# Enclosure_control.net
KiCad netlist of a schematic drawn in EAGLE
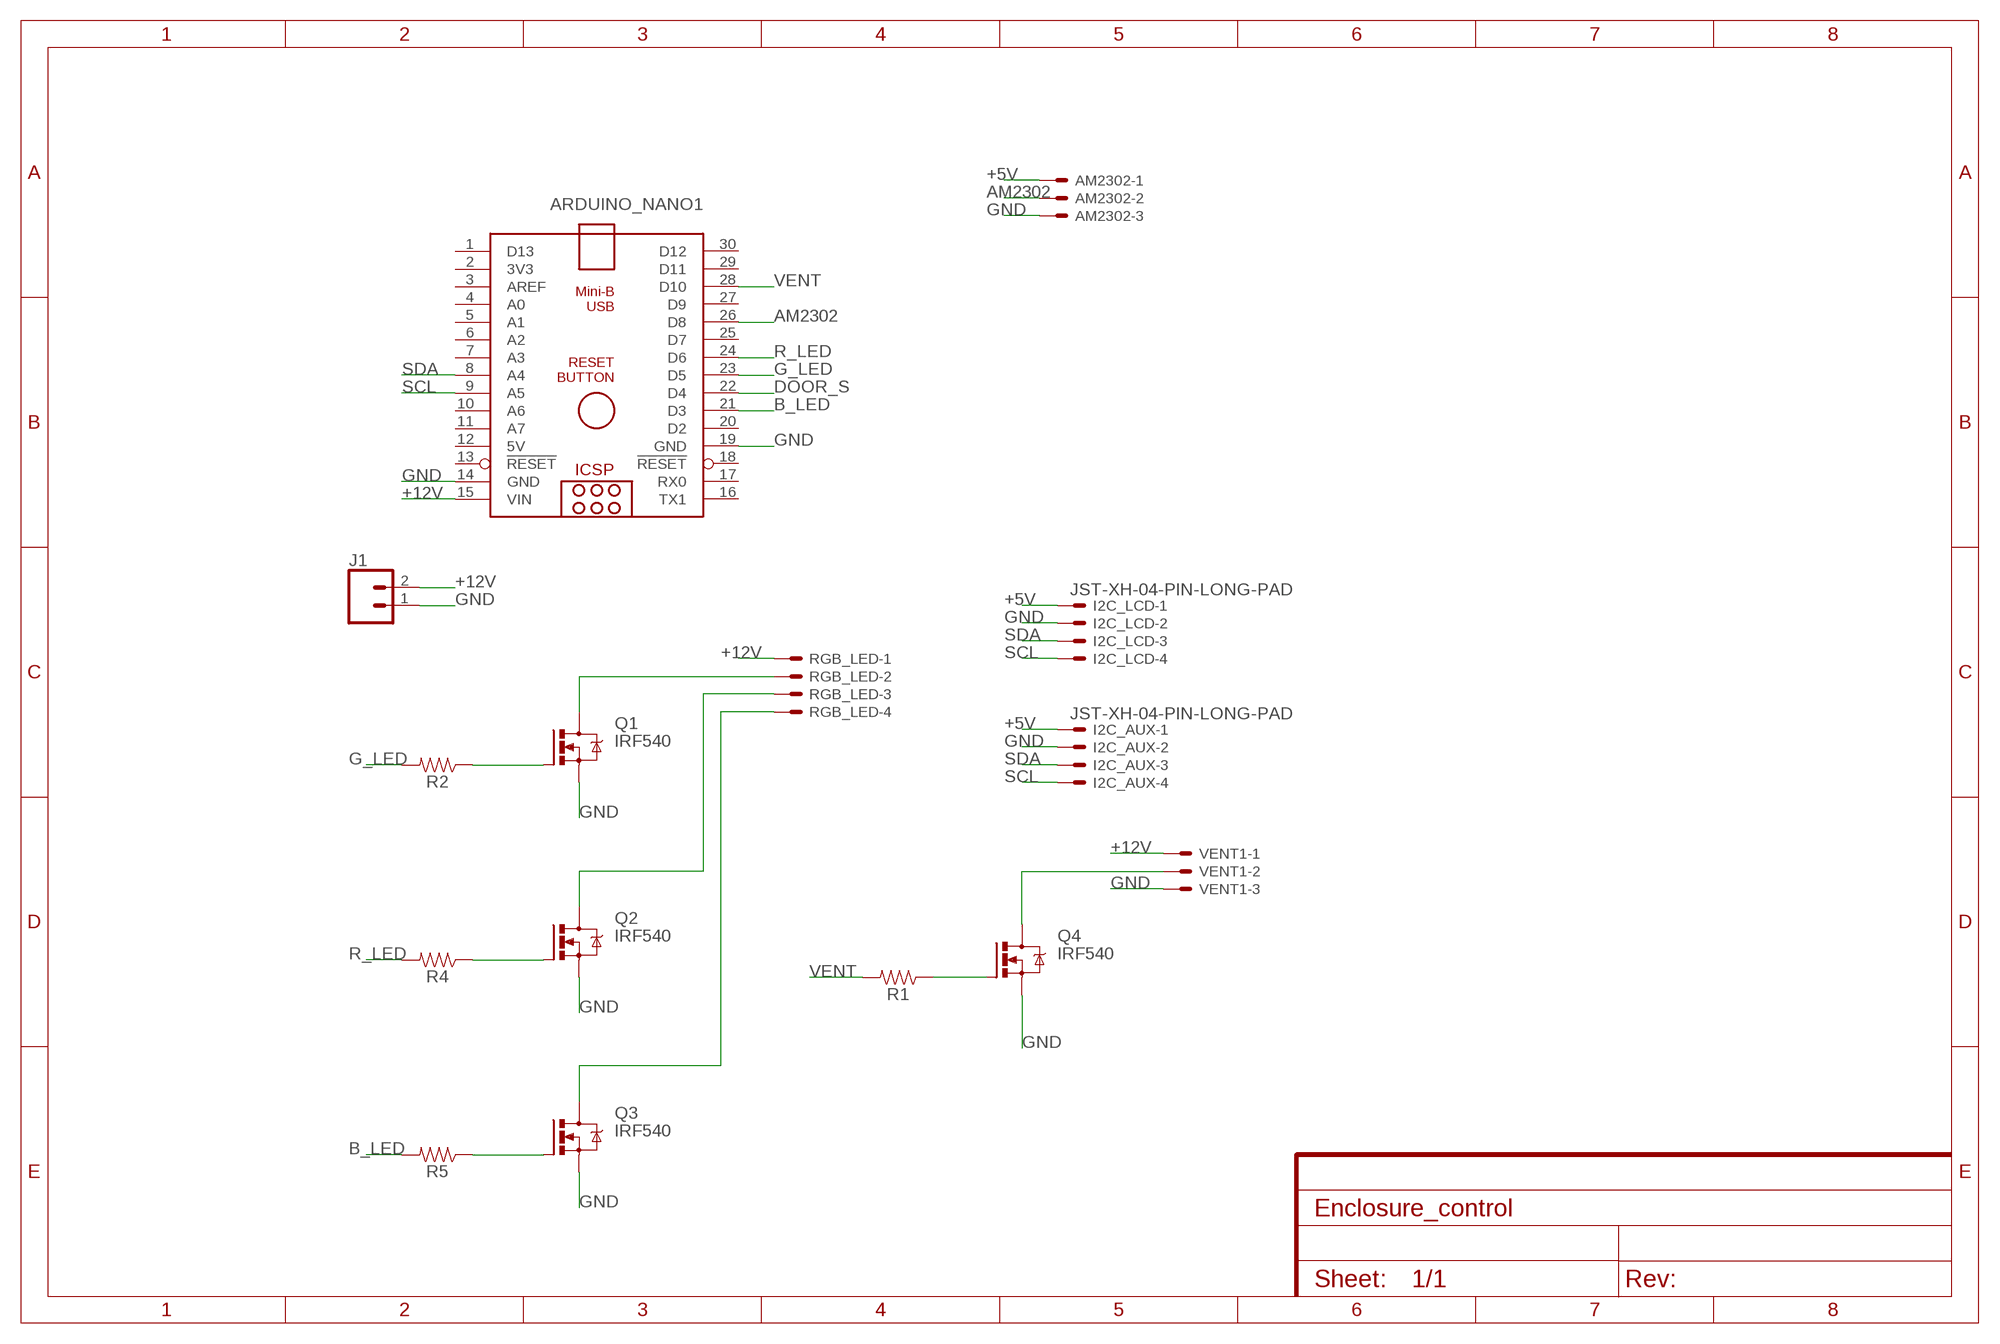
[diagram p0: schematic, sheet 1]

(export (version "E")
  (design (tool "Eeschema 10.0.6"))
  (components
    (comp (ref "AM2302")
      (value "KK-156-3")
      (footprint "eagle-import:KK-156-3")
      (fields (field (name "MF") "MOLEX"))
      (libsource (lib "eagle-import") (part "KK-156-3"))
    )
    (comp (ref "ARDUINO_NANO1")
      (value "ARDUINO_NANO")
      (footprint "eagle-import:ARDUINO_NANO")
      (libsource (lib "eagle-import") (part "ARDUINO_NANO"))
    )
    (comp (ref "I2C_AUX")
      (value "JST-XH-04-PIN-LONG-PAD")
      (footprint "eagle-import:JST-XH-04-PACKAGE-LONG-PAD")
      (libsource (lib "eagle-import") (part "JST-XH-04-PIN-LONG-PAD"))
    )
    (comp (ref "I2C_LCD")
      (value "JST-XH-04-PIN-LONG-PAD")
      (footprint "eagle-import:JST-XH-04-PACKAGE-LONG-PAD")
      (libsource (lib "eagle-import") (part "JST-XH-04-PIN-LONG-PAD"))
    )
    (comp (ref "J1")
      (value "CONN_02PTH4")
      (footprint "eagle-import:1X02_XTRA_BIG")
      (libsource (lib "eagle-import") (part "CONN_02PTH4"))
    )
    (comp (ref "Q1")
      (value "IRF540")
      (footprint "eagle-import:TO220BV")
      (libsource (lib "eagle-import") (part "IRF540"))
    )
    (comp (ref "Q2")
      (value "IRF540")
      (footprint "eagle-import:TO220BV")
      (libsource (lib "eagle-import") (part "IRF540"))
    )
    (comp (ref "Q3")
      (value "IRF540")
      (footprint "eagle-import:TO220BV")
      (libsource (lib "eagle-import") (part "IRF540"))
    )
    (comp (ref "Q4")
      (value "IRF540")
      (footprint "eagle-import:TO220BV")
      (libsource (lib "eagle-import") (part "IRF540"))
    )
    (comp (ref "R1")
      (value "RESISTORAXIAL-0.3")
      (footprint "eagle-import:AXIAL-0.3")
      (libsource (lib "eagle-import") (part "RESISTORAXIAL-0.3"))
    )
    (comp (ref "R2")
      (value "RESISTORAXIAL-0.3")
      (footprint "eagle-import:AXIAL-0.3")
      (libsource (lib "eagle-import") (part "RESISTORAXIAL-0.3"))
    )
    (comp (ref "R4")
      (value "RESISTORAXIAL-0.3")
      (footprint "eagle-import:AXIAL-0.3")
      (libsource (lib "eagle-import") (part "RESISTORAXIAL-0.3"))
    )
    (comp (ref "R5")
      (value "RESISTORAXIAL-0.3")
      (footprint "eagle-import:AXIAL-0.3")
      (libsource (lib "eagle-import") (part "RESISTORAXIAL-0.3"))
    )
    (comp (ref "RGB_LED")
      (value "KK-156-4")
      (footprint "eagle-import:KK-156-4")
      (fields (field (name "MF") "MOLEX"))
      (libsource (lib "eagle-import") (part "KK-156-4"))
    )
    (comp (ref "VENT1")
      (value "KK-156-3")
      (footprint "eagle-import:KK-156-3")
      (fields (field (name "MF") "MOLEX"))
      (libsource (lib "eagle-import") (part "KK-156-3"))
    )
  )
  (nets
    (net (code "1") (name "/+5V") (class "Default")
      (node (ref "AM2302") (pin "1") (pinfunction "S_1") (pintype "passive"))
      (node (ref "I2C_AUX") (pin "1") (pinfunction "S_1") (pintype "passive"))
      (node (ref "I2C_LCD") (pin "1") (pinfunction "S_1") (pintype "passive"))
    )
    (net (code "2") (name "/+12V") (class "Default")
      (node (ref "ARDUINO_NANO1") (pin "15") (pinfunction "VIN_15") (pintype "power_in"))
      (node (ref "J1") (pin "2") (pinfunction "2_2") (pintype "passive"))
      (node (ref "RGB_LED") (pin "1") (pinfunction "S_1") (pintype "passive"))
      (node (ref "VENT1") (pin "1") (pinfunction "S_1") (pintype "passive"))
    )
    (net (code "3") (name "/5V") (class "Default")
      (node (ref "ARDUINO_NANO1") (pin "12") (pinfunction "5V_12") (pintype "power_in"))
    )
    (net (code "4") (name "/AM2302") (class "Default")
      (node (ref "AM2302") (pin "2") (pinfunction "S_2") (pintype "passive"))
      (node (ref "ARDUINO_NANO1") (pin "26") (pinfunction "D8_26") (pintype "bidirectional"))
    )
    (net (code "5") (name "/B_LED") (class "Default")
      (node (ref "ARDUINO_NANO1") (pin "21") (pinfunction "D3_21") (pintype "bidirectional"))
      (node (ref "R5") (pin "P$2") (pinfunction "2_P$2") (pintype "passive"))
    )
    (net (code "6") (name "/DOOR_S") (class "Default")
      (node (ref "ARDUINO_NANO1") (pin "22") (pinfunction "D4_22") (pintype "bidirectional"))
    )
    (net (code "7") (name "/GND") (class "Default")
      (node (ref "AM2302") (pin "3") (pinfunction "S_3") (pintype "passive"))
      (node (ref "ARDUINO_NANO1") (pin "14") (pinfunction "GND_14") (pintype "power_in"))
      (node (ref "ARDUINO_NANO1") (pin "19") (pinfunction "GND_19") (pintype "power_in"))
      (node (ref "I2C_AUX") (pin "2") (pinfunction "S_2") (pintype "passive"))
      (node (ref "I2C_LCD") (pin "2") (pinfunction "S_2") (pintype "passive"))
      (node (ref "J1") (pin "1") (pinfunction "1_1") (pintype "passive"))
      (node (ref "Q1") (pin "S") (pinfunction "S_S") (pintype "passive"))
      (node (ref "Q2") (pin "S") (pinfunction "S_S") (pintype "passive"))
      (node (ref "Q3") (pin "S") (pinfunction "S_S") (pintype "passive"))
      (node (ref "Q4") (pin "S") (pinfunction "S_S") (pintype "passive"))
      (node (ref "VENT1") (pin "3") (pinfunction "S_3") (pintype "passive"))
    )
    (net (code "8") (name "/G_LED") (class "Default")
      (node (ref "ARDUINO_NANO1") (pin "23") (pinfunction "D5_23") (pintype "bidirectional"))
      (node (ref "R2") (pin "P$2") (pinfunction "2_P$2") (pintype "passive"))
    )
    (net (code "9") (name "/R_LED") (class "Default")
      (node (ref "ARDUINO_NANO1") (pin "24") (pinfunction "D6_24") (pintype "bidirectional"))
      (node (ref "R4") (pin "P$2") (pinfunction "2_P$2") (pintype "passive"))
    )
    (net (code "10") (name "/SCL") (class "Default")
      (node (ref "ARDUINO_NANO1") (pin "9") (pinfunction "A5_9") (pintype "bidirectional"))
      (node (ref "I2C_AUX") (pin "4") (pinfunction "S_4") (pintype "passive"))
      (node (ref "I2C_LCD") (pin "4") (pinfunction "S_4") (pintype "passive"))
    )
    (net (code "11") (name "/SDA") (class "Default")
      (node (ref "ARDUINO_NANO1") (pin "8") (pinfunction "A4_8") (pintype "bidirectional"))
      (node (ref "I2C_AUX") (pin "3") (pinfunction "S_3") (pintype "passive"))
      (node (ref "I2C_LCD") (pin "3") (pinfunction "S_3") (pintype "passive"))
    )
    (net (code "12") (name "/VENT") (class "Default")
      (node (ref "ARDUINO_NANO1") (pin "28") (pinfunction "D10_28") (pintype "bidirectional"))
      (node (ref "R1") (pin "P$2") (pinfunction "2_P$2") (pintype "passive"))
    )
    (net (code "13") (name "Net-(R1-1)") (class "Default")
      (node (ref "Q4") (pin "G") (pinfunction "G_G") (pintype "passive"))
      (node (ref "R1") (pin "P$1") (pinfunction "1_P$1") (pintype "passive"))
    )
    (net (code "14") (name "Net-(R2-1)") (class "Default")
      (node (ref "Q1") (pin "G") (pinfunction "G_G") (pintype "passive"))
      (node (ref "R2") (pin "P$1") (pinfunction "1_P$1") (pintype "passive"))
    )
    (net (code "15") (name "Net-(R4-1)") (class "Default")
      (node (ref "Q2") (pin "G") (pinfunction "G_G") (pintype "passive"))
      (node (ref "R4") (pin "P$1") (pinfunction "1_P$1") (pintype "passive"))
    )
    (net (code "16") (name "Net-(R5-1)") (class "Default")
      (node (ref "Q3") (pin "G") (pinfunction "G_G") (pintype "passive"))
      (node (ref "R5") (pin "P$1") (pinfunction "1_P$1") (pintype "passive"))
    )
    (net (code "17") (name "Net-(RGB_LEDB-S)") (class "Default")
      (node (ref "Q1") (pin "D") (pinfunction "D_D") (pintype "passive"))
      (node (ref "RGB_LED") (pin "2") (pinfunction "S_2") (pintype "passive"))
    )
    (net (code "18") (name "Net-(RGB_LEDC-S)") (class "Default")
      (node (ref "Q2") (pin "D") (pinfunction "D_D") (pintype "passive"))
      (node (ref "RGB_LED") (pin "3") (pinfunction "S_3") (pintype "passive"))
    )
    (net (code "19") (name "Net-(RGB_LEDD-S)") (class "Default")
      (node (ref "Q3") (pin "D") (pinfunction "D_D") (pintype "passive"))
      (node (ref "RGB_LED") (pin "4") (pinfunction "S_4") (pintype "passive"))
    )
    (net (code "20") (name "Net-(VENT1B-S)") (class "Default")
      (node (ref "Q4") (pin "D") (pinfunction "D_D") (pintype "passive"))
      (node (ref "VENT1") (pin "2") (pinfunction "S_2") (pintype "passive"))
    )
    (net (code "21") (name "unconnected-(ARDUINO_NANO1-3V3-Pad2)") (class "Default")
      (node (ref "ARDUINO_NANO1") (pin "2") (pinfunction "3V3_2") (pintype "output"))
    )
    (net (code "22") (name "unconnected-(ARDUINO_NANO1-A0-Pad4)") (class "Default")
      (node (ref "ARDUINO_NANO1") (pin "4") (pinfunction "A0_4") (pintype "bidirectional"))
    )
    (net (code "23") (name "unconnected-(ARDUINO_NANO1-A1-Pad5)") (class "Default")
      (node (ref "ARDUINO_NANO1") (pin "5") (pinfunction "A1_5") (pintype "bidirectional"))
    )
    (net (code "24") (name "unconnected-(ARDUINO_NANO1-A2-Pad6)") (class "Default")
      (node (ref "ARDUINO_NANO1") (pin "6") (pinfunction "A2_6") (pintype "bidirectional"))
    )
    (net (code "25") (name "unconnected-(ARDUINO_NANO1-A3-Pad7)") (class "Default")
      (node (ref "ARDUINO_NANO1") (pin "7") (pinfunction "A3_7") (pintype "bidirectional"))
    )
    (net (code "26") (name "unconnected-(ARDUINO_NANO1-A6-Pad10)") (class "Default")
      (node (ref "ARDUINO_NANO1") (pin "10") (pinfunction "A6_10") (pintype "bidirectional"))
    )
    (net (code "27") (name "unconnected-(ARDUINO_NANO1-A7-Pad11)") (class "Default")
      (node (ref "ARDUINO_NANO1") (pin "11") (pinfunction "A7_11") (pintype "bidirectional"))
    )
    (net (code "28") (name "unconnected-(ARDUINO_NANO1-AREF-Pad3)") (class "Default")
      (node (ref "ARDUINO_NANO1") (pin "3") (pinfunction "AREF_3") (pintype "input"))
    )
    (net (code "29") (name "unconnected-(ARDUINO_NANO1-D2-Pad20)") (class "Default")
      (node (ref "ARDUINO_NANO1") (pin "20") (pinfunction "D2_20") (pintype "bidirectional"))
    )
    (net (code "30") (name "unconnected-(ARDUINO_NANO1-D7-Pad25)") (class "Default")
      (node (ref "ARDUINO_NANO1") (pin "25") (pinfunction "D7_25") (pintype "bidirectional"))
    )
    (net (code "31") (name "unconnected-(ARDUINO_NANO1-D9-Pad27)") (class "Default")
      (node (ref "ARDUINO_NANO1") (pin "27") (pinfunction "D9_27") (pintype "bidirectional"))
    )
    (net (code "32") (name "unconnected-(ARDUINO_NANO1-D11-Pad29)") (class "Default")
      (node (ref "ARDUINO_NANO1") (pin "29") (pinfunction "D11_29") (pintype "bidirectional"))
    )
    (net (code "33") (name "unconnected-(ARDUINO_NANO1-D12-Pad30)") (class "Default")
      (node (ref "ARDUINO_NANO1") (pin "30") (pinfunction "D12_30") (pintype "bidirectional"))
    )
    (net (code "34") (name "unconnected-(ARDUINO_NANO1-D13-Pad1)") (class "Default")
      (node (ref "ARDUINO_NANO1") (pin "1") (pinfunction "D13_1") (pintype "bidirectional"))
    )
    (net (code "35") (name "unconnected-(ARDUINO_NANO1-RX0-Pad17)") (class "Default")
      (node (ref "ARDUINO_NANO1") (pin "17") (pinfunction "RX0_17") (pintype "bidirectional"))
    )
    (net (code "36") (name "unconnected-(ARDUINO_NANO1-TX1-Pad16)") (class "Default")
      (node (ref "ARDUINO_NANO1") (pin "16") (pinfunction "TX1_16") (pintype "bidirectional"))
    )
    (net (code "37") (name "unconnected-(ARDUINO_NANO1-~{RESET}-Pad13)") (class "Default")
      (node (ref "ARDUINO_NANO1") (pin "13") (pinfunction "~{RESET}_13") (pintype "input"))
    )
    (net (code "38") (name "unconnected-(ARDUINO_NANO1-~{RESET}-Pad18)") (class "Default")
      (node (ref "ARDUINO_NANO1") (pin "18") (pinfunction "~{RESET}_18") (pintype "input"))
    )
  )
)
